# Ethernet_Roer.net
KiCad netlist of a schematic drawn in EasyEDA
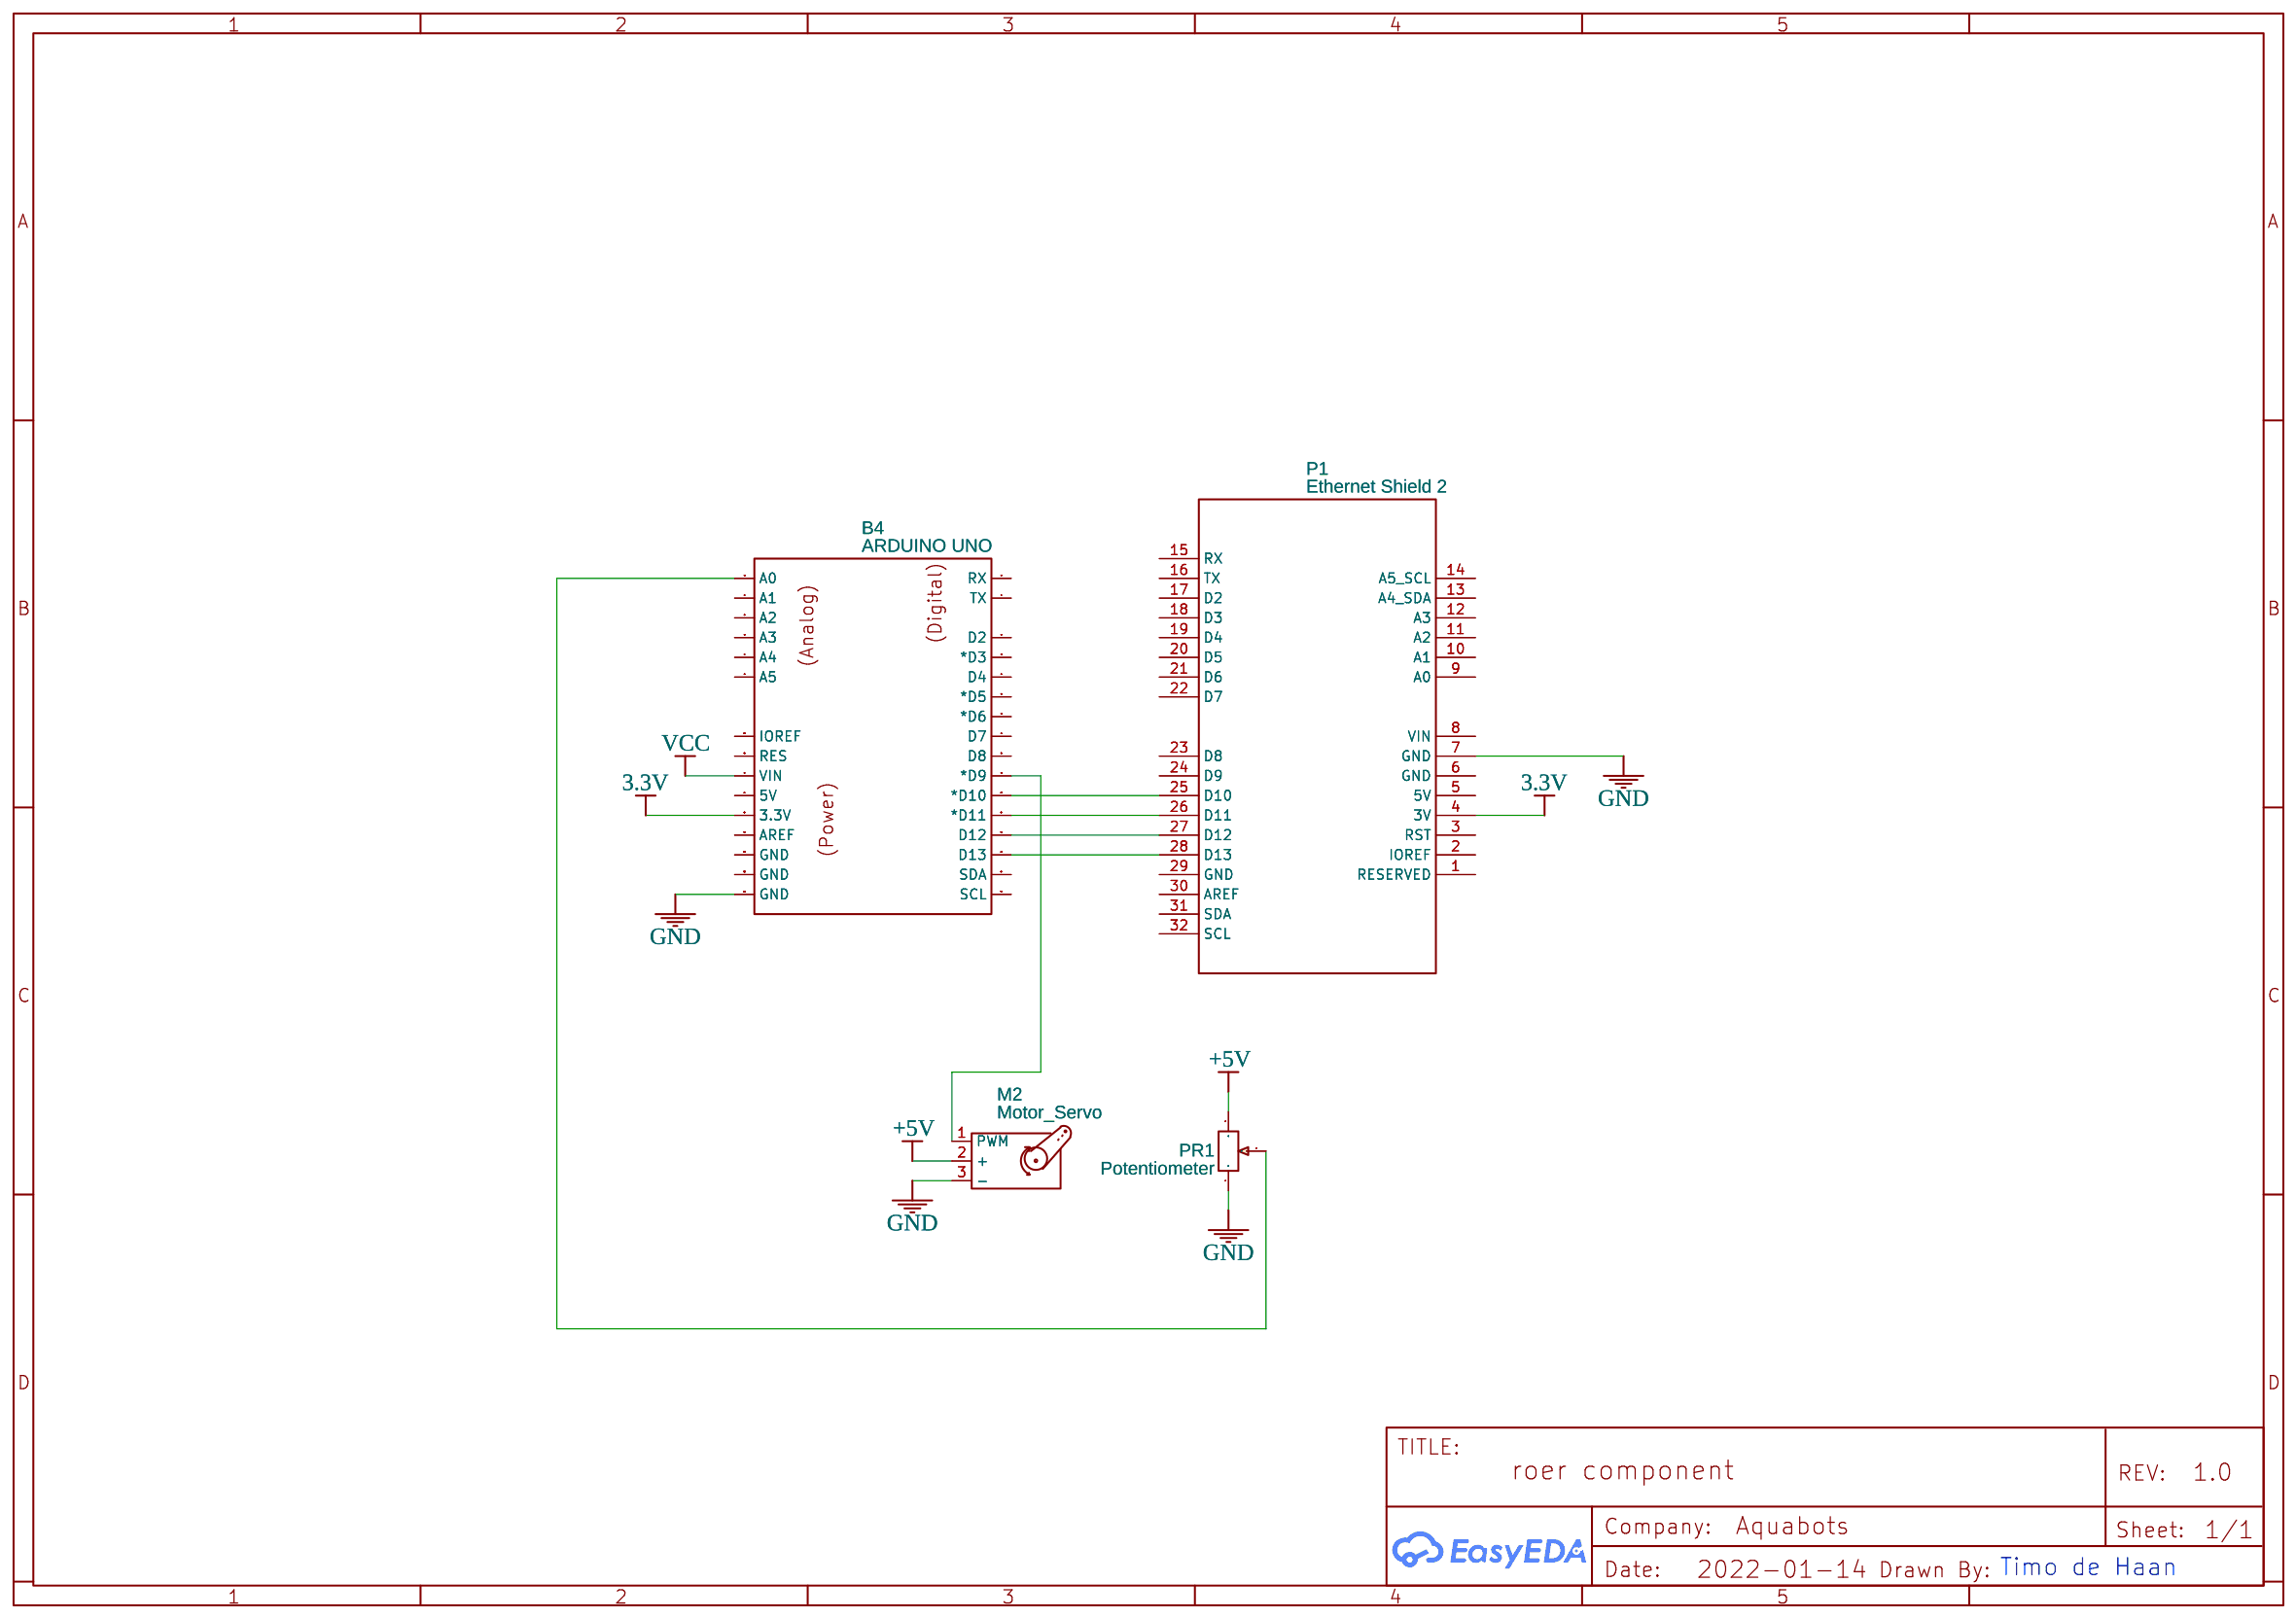
[diagram p0: schematic sheet]

(export (version "E")
  (design (tool "Eeschema 10.0.6"))
  (components
    (comp (ref "B4")
      (value "ARDUINO UNO")
      (fields (field (name "Manufacturer") "?"))
      (libsource (lib "") (part "ARDUINO UNO R3 SHIELD"))
    )
    (comp (ref "M2") (value "Motor_Servo") (libsource (lib "") (part "Motor_Servo")))
    (comp (ref "P1") (value "Ethernet Shield 2") (libsource (lib "") (part "Ethernet Shield 2")))
    (comp (ref "PR1")
      (value "Potentiometer")
      (fields
        (field (name "BOM_Manufacturer Part") "Potentiometer WH160-1-104")
        (field (name "BOM_Supplier Part") "C61836")
      )
      (libsource (lib "") (part "Potentiometer"))
    )
  )
  (nets
    (net (code "1") (name "+5V") (class "Default")
      (node (ref "M2") (pin "2") (pinfunction "+_2") (pintype "unspecified"))
      (node (ref "PR1") (pin "3") (pinfunction "3_3") (pintype "input"))
    )
    (net (code "2") (name "3.3V") (class "Default")
      (node (ref "B4") (pin "3.3V") (pinfunction "3.3V_3.3V") (pintype "unspecified"))
      (node (ref "P1") (pin "4") (pinfunction "3V_4") (pintype "unspecified"))
    )
    (net (code "3") (name "GND") (class "Default")
      (node (ref "B4") (pin "GND@0") (pinfunction "GND_GND@0") (pintype "unspecified"))
      (node (ref "M2") (pin "3") (pinfunction "-_3") (pintype "unspecified"))
      (node (ref "P1") (pin "7") (pinfunction "GND_7") (pintype "unspecified"))
      (node (ref "PR1") (pin "1") (pinfunction "1_1") (pintype "input"))
    )
    (net (code "4") (name "Net-(B4-*D9)") (class "Default")
      (node (ref "B4") (pin "D9") (pinfunction "*D9_D9") (pintype "unspecified"))
      (node (ref "M2") (pin "1") (pinfunction "PWM_1") (pintype "unspecified"))
    )
    (net (code "5") (name "Net-(B4-*D10)") (class "Default")
      (node (ref "B4") (pin "D10") (pinfunction "*D10_D10") (pintype "unspecified"))
      (node (ref "P1") (pin "25") (pinfunction "D10_25") (pintype "unspecified"))
    )
    (net (code "6") (name "Net-(B4-*D11)") (class "Default")
      (node (ref "B4") (pin "D11") (pinfunction "*D11_D11") (pintype "unspecified"))
      (node (ref "P1") (pin "26") (pinfunction "D11_26") (pintype "unspecified"))
    )
    (net (code "7") (name "Net-(B4-PadA0)") (class "Default")
      (node (ref "B4") (pin "A0") (pinfunction "A0_A0") (pintype "unspecified"))
      (node (ref "PR1") (pin "2") (pinfunction "2_2") (pintype "input"))
    )
    (net (code "8") (name "Net-(P1-D12)") (class "Default")
      (node (ref "B4") (pin "D12") (pinfunction "D12_D12") (pintype "unspecified"))
      (node (ref "P1") (pin "27") (pinfunction "D12_27") (pintype "unspecified"))
    )
    (net (code "9") (name "Net-(P1-D13)") (class "Default")
      (node (ref "B4") (pin "D13") (pinfunction "D13_D13") (pintype "unspecified"))
      (node (ref "P1") (pin "28") (pinfunction "D13_28") (pintype "unspecified"))
    )
    (net (code "10") (name "VCC") (class "Default")
      (node (ref "B4") (pin "VIN") (pinfunction "VIN_VIN") (pintype "unspecified"))
    )
    (net (code "11") (name "unconnected-(B4-*D3-PadD3)") (class "Default")
      (node (ref "B4") (pin "D3") (pinfunction "*D3_D3") (pintype "unspecified"))
    )
    (net (code "12") (name "unconnected-(B4-*D5-PadD5)") (class "Default")
      (node (ref "B4") (pin "D5") (pinfunction "*D5_D5") (pintype "unspecified"))
    )
    (net (code "13") (name "unconnected-(B4-*D6-PadD6)") (class "Default")
      (node (ref "B4") (pin "D6") (pinfunction "*D6_D6") (pintype "unspecified"))
    )
    (net (code "14") (name "unconnected-(B4-GND-PadGND@1)") (class "Default")
      (node (ref "B4") (pin "GND@1") (pinfunction "GND_GND@1") (pintype "unspecified"))
    )
    (net (code "15") (name "unconnected-(B4-GND-PadGND@2)") (class "Default")
      (node (ref "B4") (pin "GND@2") (pinfunction "GND_GND@2") (pintype "unspecified"))
    )
    (net (code "16") (name "unconnected-(B4-Pad5V)") (class "Default")
      (node (ref "B4") (pin "5V") (pinfunction "5V_5V") (pintype "unspecified"))
    )
    (net (code "17") (name "unconnected-(B4-PadA1)") (class "Default")
      (node (ref "B4") (pin "A1") (pinfunction "A1_A1") (pintype "unspecified"))
    )
    (net (code "18") (name "unconnected-(B4-PadA2)") (class "Default")
      (node (ref "B4") (pin "A2") (pinfunction "A2_A2") (pintype "unspecified"))
    )
    (net (code "19") (name "unconnected-(B4-PadA3)") (class "Default")
      (node (ref "B4") (pin "A3") (pinfunction "A3_A3") (pintype "unspecified"))
    )
    (net (code "20") (name "unconnected-(B4-PadA4)") (class "Default")
      (node (ref "B4") (pin "A4") (pinfunction "A4_A4") (pintype "unspecified"))
    )
    (net (code "21") (name "unconnected-(B4-PadA5)") (class "Default")
      (node (ref "B4") (pin "A5") (pinfunction "A5_A5") (pintype "unspecified"))
    )
    (net (code "22") (name "unconnected-(B4-PadAREF)") (class "Default")
      (node (ref "B4") (pin "AREF") (pinfunction "AREF_AREF") (pintype "unspecified"))
    )
    (net (code "23") (name "unconnected-(B4-PadD2)") (class "Default")
      (node (ref "B4") (pin "D2") (pinfunction "D2_D2") (pintype "unspecified"))
    )
    (net (code "24") (name "unconnected-(B4-PadD4)") (class "Default")
      (node (ref "B4") (pin "D4") (pinfunction "D4_D4") (pintype "unspecified"))
    )
    (net (code "25") (name "unconnected-(B4-PadD7)") (class "Default")
      (node (ref "B4") (pin "D7") (pinfunction "D7_D7") (pintype "unspecified"))
    )
    (net (code "26") (name "unconnected-(B4-PadD8)") (class "Default")
      (node (ref "B4") (pin "D8") (pinfunction "D8_D8") (pintype "unspecified"))
    )
    (net (code "27") (name "unconnected-(B4-PadIOREF)") (class "Default")
      (node (ref "B4") (pin "IOREF") (pinfunction "IOREF_IOREF") (pintype "unspecified"))
    )
    (net (code "28") (name "unconnected-(B4-PadRES)") (class "Default")
      (node (ref "B4") (pin "RES") (pinfunction "RES_RES") (pintype "unspecified"))
    )
    (net (code "29") (name "unconnected-(B4-PadRX)") (class "Default")
      (node (ref "B4") (pin "RX") (pinfunction "RX_RX") (pintype "unspecified"))
    )
    (net (code "30") (name "unconnected-(B4-PadSCL)") (class "Default")
      (node (ref "B4") (pin "SCL") (pinfunction "SCL_SCL") (pintype "unspecified"))
    )
    (net (code "31") (name "unconnected-(B4-PadSDA)") (class "Default")
      (node (ref "B4") (pin "SDA") (pinfunction "SDA_SDA") (pintype "unspecified"))
    )
    (net (code "32") (name "unconnected-(B4-PadTX)") (class "Default")
      (node (ref "B4") (pin "TX") (pinfunction "TX_TX") (pintype "unspecified"))
    )
    (net (code "33") (name "unconnected-(P1-5V-Pad5)") (class "Default")
      (node (ref "P1") (pin "5") (pinfunction "5V_5") (pintype "unspecified"))
    )
    (net (code "34") (name "unconnected-(P1-A0-Pad9)") (class "Default")
      (node (ref "P1") (pin "9") (pinfunction "A0_9") (pintype "unspecified"))
    )
    (net (code "35") (name "unconnected-(P1-A1-Pad10)") (class "Default")
      (node (ref "P1") (pin "10") (pinfunction "A1_10") (pintype "unspecified"))
    )
    (net (code "36") (name "unconnected-(P1-A2-Pad11)") (class "Default")
      (node (ref "P1") (pin "11") (pinfunction "A2_11") (pintype "unspecified"))
    )
    (net (code "37") (name "unconnected-(P1-A3-Pad12)") (class "Default")
      (node (ref "P1") (pin "12") (pinfunction "A3_12") (pintype "unspecified"))
    )
    (net (code "38") (name "unconnected-(P1-A4_SDA-Pad13)") (class "Default")
      (node (ref "P1") (pin "13") (pinfunction "A4_SDA_13") (pintype "unspecified"))
    )
    (net (code "39") (name "unconnected-(P1-A5_SCL-Pad14)") (class "Default")
      (node (ref "P1") (pin "14") (pinfunction "A5_SCL_14") (pintype "unspecified"))
    )
    (net (code "40") (name "unconnected-(P1-AREF-Pad30)") (class "Default")
      (node (ref "P1") (pin "30") (pinfunction "AREF_30") (pintype "unspecified"))
    )
    (net (code "41") (name "unconnected-(P1-D2-Pad17)") (class "Default")
      (node (ref "P1") (pin "17") (pinfunction "D2_17") (pintype "unspecified"))
    )
    (net (code "42") (name "unconnected-(P1-D3-Pad18)") (class "Default")
      (node (ref "P1") (pin "18") (pinfunction "D3_18") (pintype "unspecified"))
    )
    (net (code "43") (name "unconnected-(P1-D4-Pad19)") (class "Default")
      (node (ref "P1") (pin "19") (pinfunction "D4_19") (pintype "unspecified"))
    )
    (net (code "44") (name "unconnected-(P1-D5-Pad20)") (class "Default")
      (node (ref "P1") (pin "20") (pinfunction "D5_20") (pintype "unspecified"))
    )
    (net (code "45") (name "unconnected-(P1-D6-Pad21)") (class "Default")
      (node (ref "P1") (pin "21") (pinfunction "D6_21") (pintype "unspecified"))
    )
    (net (code "46") (name "unconnected-(P1-D7-Pad22)") (class "Default")
      (node (ref "P1") (pin "22") (pinfunction "D7_22") (pintype "unspecified"))
    )
    (net (code "47") (name "unconnected-(P1-D8-Pad23)") (class "Default")
      (node (ref "P1") (pin "23") (pinfunction "D8_23") (pintype "unspecified"))
    )
    (net (code "48") (name "unconnected-(P1-D9-Pad24)") (class "Default")
      (node (ref "P1") (pin "24") (pinfunction "D9_24") (pintype "unspecified"))
    )
    (net (code "49") (name "unconnected-(P1-GND-Pad6)") (class "Default")
      (node (ref "P1") (pin "6") (pinfunction "GND_6") (pintype "unspecified"))
    )
    (net (code "50") (name "unconnected-(P1-GND-Pad29)") (class "Default")
      (node (ref "P1") (pin "29") (pinfunction "GND_29") (pintype "unspecified"))
    )
    (net (code "51") (name "unconnected-(P1-IOREF-Pad2)") (class "Default")
      (node (ref "P1") (pin "2") (pinfunction "IOREF_2") (pintype "unspecified"))
    )
    (net (code "52") (name "unconnected-(P1-RESERVED-Pad1)") (class "Default")
      (node (ref "P1") (pin "1") (pinfunction "RESERVED_1") (pintype "unspecified"))
    )
    (net (code "53") (name "unconnected-(P1-RST-Pad3)") (class "Default")
      (node (ref "P1") (pin "3") (pinfunction "RST_3") (pintype "unspecified"))
    )
    (net (code "54") (name "unconnected-(P1-RX-Pad15)") (class "Default")
      (node (ref "P1") (pin "15") (pinfunction "RX_15") (pintype "unspecified"))
    )
    (net (code "55") (name "unconnected-(P1-SCL-Pad32)") (class "Default")
      (node (ref "P1") (pin "32") (pinfunction "SCL_32") (pintype "unspecified"))
    )
    (net (code "56") (name "unconnected-(P1-SDA-Pad31)") (class "Default")
      (node (ref "P1") (pin "31") (pinfunction "SDA_31") (pintype "unspecified"))
    )
    (net (code "57") (name "unconnected-(P1-TX-Pad16)") (class "Default")
      (node (ref "P1") (pin "16") (pinfunction "TX_16") (pintype "unspecified"))
    )
    (net (code "58") (name "unconnected-(P1-VIN-Pad8)") (class "Default")
      (node (ref "P1") (pin "8") (pinfunction "VIN_8") (pintype "unspecified"))
    )
  )
)
